# DC-DC.net
KiCad netlist of a schematic drawn in Altium Designer
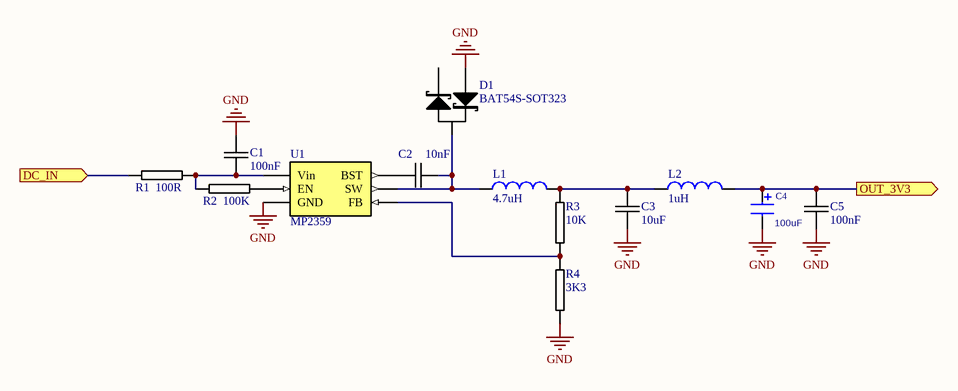
[diagram p0: DC-DC.SchDoc]

(export (version "E")
  (design (tool "Eeschema 10.0.6"))
  (components
    (comp (ref "C1")
      (value "100nF")
      (footprint "0603C-GENERIC")
      (description "CAPACITOR 0603 CERAMIC")
      (fields
        (field (name "MANUFACTURER PART NUMBER") "C1608X7R1E104K")
        (field (name "MANUFACTURER") "TDK Corporation")
      )
      (libsource (lib "vh_altium_library") (part "0603C-100NF-25V-X7R-TDK"))
    )
    (comp (ref "C2")
      (value "10nF")
      (footprint "0603C-GENERIC")
      (description "CAPACITOR 0603 CERAMIC")
      (fields
        (field (name "MANUFACTURER PART NUMBER") "GRM188R71H103KA01D")
        (field (name "MANUFACTURER") "Murata Electronics North America")
      )
      (libsource (lib "vh_altium_library") (part "0603C-10NF-50V-X7R-MUR"))
    )
    (comp (ref "C3")
      (value "10uF")
      (footprint "0805C-GENERIC")
      (description "CAPACITOR 0805 CERAMIC")
      (fields (field (name "TOLERANCE") "±20%") (field (name "MANUFACTURER") "Panasonic - ECG"))
      (libsource (lib "vh_altium_library") (part "0805C-10UF-6V3-X5R-PAN"))
    )
    (comp (ref "C4")
      (value "100uF")
      (footprint "CPM7343")
      (description "Capacitor")
      (libsource (lib "AX_Altium_v2.3") (part "CPM7343"))
    )
    (comp (ref "C5")
      (value "100nF")
      (footprint "0603C-GENERIC")
      (description "CAPACITOR 0603 CERAMIC")
      (fields
        (field (name "MANUFACTURER PART NUMBER") "C1608X7R1E104K")
        (field (name "MANUFACTURER") "TDK Corporation")
      )
      (libsource (lib "vh_altium_library") (part "0603C-100NF-25V-X7R-TDK"))
    )
    (comp (ref "D1")
      (value "BAT54S-SOT323")
      (footprint "SOT323-123")
      (description "DUAL SCHOTTKY DIODE SERIES")
      (fields
        (field (name "MANUFACTURER") "NXP Semiconductors")
        (field (name "MANUFACTURER PART NUMBER") "BAT54SW,115")
      )
      (libsource (lib "vh_altium_library") (part "BAT54S-SOT323"))
    )
    (comp (ref "L1")
      (value "IND")
      (footprint "C_1210")
      (fields (field (name "INDUCTANCE") "4.7uH"))
      (libsource (lib "MyLibAltium_v1") (part "Inductor"))
    )
    (comp (ref "L2")
      (value "IND")
      (footprint "C_1206")
      (fields (field (name "INDUCTANCE") "1uH"))
      (libsource (lib "MyLibAltium_v1") (part "Inductor"))
    )
    (comp (ref "R1")
      (value "100R")
      (footprint "0603R-100")
      (description "GENERIC RESISTOR 0603")
      (fields
        (field (name "MANUFACTURER PART NUMBER") "RMCF 1/16 100 1% R")
        (field (name "MANUFACTURER") "Stackpole Electronics Inc")
      )
      (libsource (lib "vh_altium_library") (part "0603R-100"))
    )
    (comp (ref "R2")
      (value "100K")
      (footprint "0603R-100K")
      (description "GENERIC RESISTOR 0603")
      (fields
        (field (name "TOLERANCE") "±1%")
        (field (name "MANUFACTURER PART NUMBER") "RMCF 1/16 100K 1% R")
      )
      (libsource (lib "vh_altium_library") (part "0603R-100K"))
    )
    (comp (ref "R3")
      (value "10K")
      (footprint "0603R-10K")
      (description "GENERIC RESISTOR 0603")
      (fields (field (name "MANUFACTURER") "Stackpole Electronics Inc") (field (name "TOLERANCE") "±1%"))
      (libsource (lib "vh_altium_library") (part "0603R-10K"))
    )
    (comp (ref "R4")
      (value "3K3")
      (footprint "0603R-GENERIC")
      (description "GENERIC RESISTOR 0603")
      (libsource (lib "vh_altium_library") (part "0603R-3K3"))
    )
    (comp (ref "U1")
      (value "MP2359")
      (footprint "TSOP23-6")
      (description "monolithic step-down switch  mode converter with a built-in power MOSFET")
      (libsource (lib "MyLibAltium_v1") (part "MP2359"))
    )
  )
  (nets
    (net (code "1") (name "/DC_IN") (class "Default") (node (ref "R1") (pin "1") (pintype "passive")))
    (net (code "2") (name "/OUT_3V3") (class "Default")
      (node (ref "C4") (pin "1") (pinfunction "1_1") (pintype "passive"))
      (node (ref "C5") (pin "1") (pintype "passive"))
      (node (ref "L2") (pin "2") (pinfunction "2_2") (pintype "passive"))
    )
    (net (code "3") (name "GND") (class "Default")
      (node (ref "C1") (pin "1") (pintype "passive"))
      (node (ref "C3") (pin "2") (pintype "passive"))
      (node (ref "C4") (pin "2") (pinfunction "2_2") (pintype "passive"))
      (node (ref "C5") (pin "2") (pintype "passive"))
      (node (ref "D1") (pin "1") (pinfunction "1_1") (pintype "passive"))
      (node (ref "R4") (pin "2") (pintype "passive"))
      (node (ref "U1") (pin "2") (pinfunction "GND_2") (pintype "power_in"))
    )
    (net (code "4") (name "Net-(C3-Pad1)") (class "Default")
      (node (ref "C3") (pin "1") (pintype "passive"))
      (node (ref "L1") (pin "2") (pinfunction "2_2") (pintype "passive"))
      (node (ref "L2") (pin "1") (pinfunction "1_1") (pintype "passive"))
      (node (ref "R3") (pin "1") (pintype "passive"))
    )
    (net (code "5") (name "Net-(U1-BST)") (class "Default")
      (node (ref "C2") (pin "1") (pintype "passive"))
      (node (ref "U1") (pin "1") (pinfunction "BST_1") (pintype "output"))
    )
    (net (code "6") (name "Net-(U1-EN)") (class "Default")
      (node (ref "R2") (pin "2") (pintype "passive"))
      (node (ref "U1") (pin "4") (pinfunction "EN_4") (pintype "input"))
    )
    (net (code "7") (name "Net-(U1-FB)") (class "Default")
      (node (ref "R3") (pin "2") (pintype "passive"))
      (node (ref "R4") (pin "1") (pintype "passive"))
      (node (ref "U1") (pin "3") (pinfunction "FB_3") (pintype "input"))
    )
    (net (code "8") (name "Net-(U1-SW)") (class "Default")
      (node (ref "C2") (pin "2") (pintype "passive"))
      (node (ref "D1") (pin "3") (pinfunction "3_3") (pintype "passive"))
      (node (ref "L1") (pin "1") (pinfunction "1_1") (pintype "passive"))
      (node (ref "U1") (pin "6") (pinfunction "SW_6") (pintype "output"))
    )
    (net (code "9") (name "Net-(U1-Vin)") (class "Default")
      (node (ref "C1") (pin "2") (pintype "passive"))
      (node (ref "R1") (pin "2") (pintype "passive"))
      (node (ref "R2") (pin "1") (pintype "passive"))
      (node (ref "U1") (pin "5") (pinfunction "Vin_5") (pintype "power_in"))
    )
    (net (code "10") (name "unconnected-(D1-Pad2)") (class "Default")
      (node (ref "D1") (pin "2") (pinfunction "2_2") (pintype "passive"))
    )
  )
)
